# ICM20602.net
KiCad netlist of a schematic drawn in Altium Designer
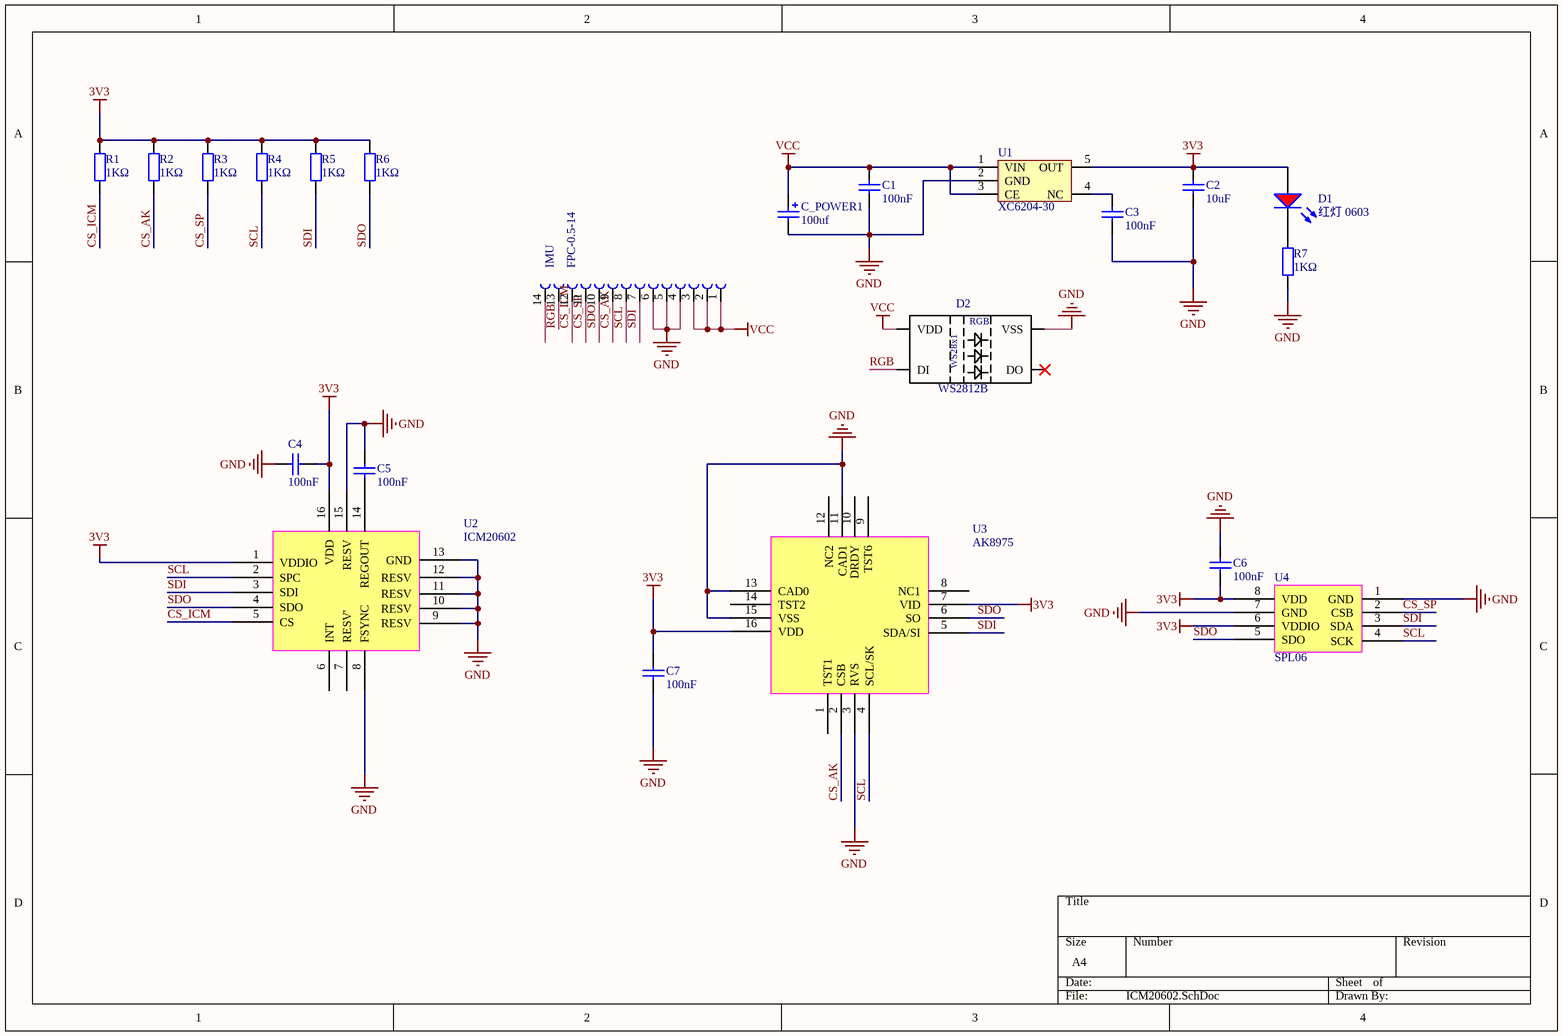
[diagram p0: ICM20602.SchDoc]

(export (version "E")
  (design (tool "Eeschema 10.0.6"))
  (components
    (comp (ref "C1")
      (value "100nF")
      (footprint "0603_C")
      (description "贴片电容")
      (libsource (lib "Miscellaneous Devices LC") (part "0603 100nF (104) 10% 50V"))
    )
    (comp (ref "C2")
      (value "10uF")
      (footprint "0603_C")
      (description "贴片电容")
      (libsource (lib "Miscellaneous Devices LC") (part "0603 10uF (106) 10% 10V"))
    )
    (comp (ref "C3")
      (value "100nF")
      (footprint "0603_C")
      (description "贴片电容")
      (libsource (lib "Miscellaneous Devices LC") (part "0603 100nF (104) 10% 50V"))
    )
    (comp (ref "C4")
      (value "100nF")
      (footprint "0603_C")
      (description "贴片电容")
      (libsource (lib "Miscellaneous Devices LC") (part "0603 100nF (104) 10% 50V"))
    )
    (comp (ref "C5")
      (value "100nF")
      (footprint "0603_C")
      (description "贴片电容")
      (libsource (lib "Miscellaneous Devices LC") (part "0603 100nF (104) 10% 50V"))
    )
    (comp (ref "C6")
      (value "100nF")
      (footprint "0603_C")
      (description "贴片电容")
      (libsource (lib "Miscellaneous Devices LC") (part "0603 100nF (104) 10% 50V"))
    )
    (comp (ref "C7")
      (value "100nF")
      (footprint "0603_C")
      (description "贴片电容")
      (libsource (lib "Miscellaneous Devices LC") (part "0603 100nF (104) 10% 50V"))
    )
    (comp (ref "C_POWER1")
      (value "100uf")
      (footprint "C1206")
      (description "Polarized Capacitor (Surface Mount)")
      (fields (field (name "PUBLISHER") "Altium Limited"))
      (libsource (lib "fly_smart") (part "Cap Pol3"))
    )
    (comp (ref "D1")
      (value "红灯 0603")
      (footprint "0603_LED_S1")
      (description "发光二极管")
      (libsource (lib "Miscellaneous Devices LC") (part "0603 红灯"))
    )
    (comp (ref "D2")
      (value "WS2812B")
      (footprint "WS2812B")
      (description "Intelligent Control Led Integrated Light Source Pack Of 10")
      (fields (field (name "MF") "Seeed Technology"))
      (libsource (lib "MyLib") (part "WS2812B"))
    )
    (comp (ref "IMU")
      (value "FPC-0.5-14")
      (footprint "FPC-0.5-14")
      (description "FFC / FPC Board Connector, WR-FPC Series, Surface Mount, Receptacle, 14, Bottom, 0.5 mm")
      (fields (field (name "MP") "687114149022") (field (name "MF") "Wurth Electronics"))
      (libsource (lib "MyLib") (part "FPC-0.5-14"))
    )
    (comp (ref "R1")
      (value "1KΩ")
      (footprint "0603_R")
      (description "贴片电阻")
      (libsource (lib "Miscellaneous Devices LC") (part "0603 1KΩ (1001) 1%"))
    )
    (comp (ref "R2")
      (value "1KΩ")
      (footprint "0603_R")
      (description "贴片电阻")
      (libsource (lib "Miscellaneous Devices LC") (part "0603 1KΩ (1001) 1%"))
    )
    (comp (ref "R3")
      (value "1KΩ")
      (footprint "0603_R")
      (description "贴片电阻")
      (libsource (lib "Miscellaneous Devices LC") (part "0603 1KΩ (1001) 1%"))
    )
    (comp (ref "R4")
      (value "1KΩ")
      (footprint "0603_R")
      (description "贴片电阻")
      (libsource (lib "Miscellaneous Devices LC") (part "0603 1KΩ (1001) 1%"))
    )
    (comp (ref "R5")
      (value "1KΩ")
      (footprint "0603_R")
      (description "贴片电阻")
      (libsource (lib "Miscellaneous Devices LC") (part "0603 1KΩ (1001) 1%"))
    )
    (comp (ref "R6")
      (value "1KΩ")
      (footprint "0603_R")
      (description "贴片电阻")
      (libsource (lib "Miscellaneous Devices LC") (part "0603 1KΩ (1001) 1%"))
    )
    (comp (ref "R7")
      (value "1KΩ")
      (footprint "0603_R")
      (description "贴片电阻")
      (libsource (lib "Miscellaneous Devices LC") (part "0603 1KΩ (1001) 1%"))
    )
    (comp (ref "U1") (value "XC6204-30") (footprint "SOT23-5S") (libsource (lib "MiniFly ") (part "XC6204")))
    (comp (ref "U2")
      (value "ICM20602")
      (footprint "ICM20602")
      (libsource (lib "TM4C_Series") (part "ICM20602"))
    )
    (comp (ref "U3") (value "AK8975") (footprint "AK8975") (libsource (lib "TM4C_Series") (part "AK8975")))
    (comp (ref "U4") (value "SPL06") (footprint "LGA-2_5X2MM") (libsource (lib "TM4C_Series") (part "SPL06")))
  )
  (nets
    (net (code "1") (name "/CS_AK") (class "Default")
      (node (ref "IMU") (pin "9") (pinfunction "6_9") (pintype "passive"))
      (node (ref "R2") (pin "1") (pinfunction "1_1") (pintype "passive"))
      (node (ref "U3") (pin "2") (pinfunction "CSB_2") (pintype "passive"))
    )
    (net (code "2") (name "/CS_ICM") (class "Default")
      (node (ref "IMU") (pin "12") (pinfunction "3_12") (pintype "passive"))
      (node (ref "R1") (pin "1") (pinfunction "1_1") (pintype "passive"))
      (node (ref "U2") (pin "5") (pinfunction "CS_5") (pintype "passive"))
    )
    (net (code "3") (name "/CS_SP") (class "Default")
      (node (ref "IMU") (pin "11") (pinfunction "4_11") (pintype "passive"))
      (node (ref "R3") (pin "1") (pinfunction "1_1") (pintype "passive"))
      (node (ref "U4") (pin "2") (pinfunction "CSB_2") (pintype "passive"))
    )
    (net (code "4") (name "/RGB") (class "Default")
      (node (ref "D2") (pin "4") (pinfunction "DI_4") (pintype "bidirectional"))
      (node (ref "IMU") (pin "13") (pinfunction "2_13") (pintype "passive"))
    )
    (net (code "5") (name "/SCL") (class "Default")
      (node (ref "IMU") (pin "8") (pinfunction "7_8") (pintype "passive"))
      (node (ref "R4") (pin "1") (pinfunction "1_1") (pintype "passive"))
      (node (ref "U2") (pin "2") (pinfunction "SPC_2") (pintype "passive"))
      (node (ref "U3") (pin "4") (pinfunction "SCL/SK_4") (pintype "passive"))
      (node (ref "U4") (pin "4") (pinfunction "SCK_4") (pintype "passive"))
    )
    (net (code "6") (name "/SDI") (class "Default")
      (node (ref "IMU") (pin "7") (pinfunction "8_7") (pintype "passive"))
      (node (ref "R5") (pin "1") (pinfunction "1_1") (pintype "passive"))
      (node (ref "U2") (pin "3") (pinfunction "SDI_3") (pintype "passive"))
      (node (ref "U3") (pin "5") (pinfunction "SDA/SI_5") (pintype "passive"))
      (node (ref "U4") (pin "3") (pinfunction "SDA_3") (pintype "passive"))
    )
    (net (code "7") (name "/SDO") (class "Default")
      (node (ref "IMU") (pin "10") (pinfunction "5_10") (pintype "passive"))
      (node (ref "R6") (pin "1") (pinfunction "1_1") (pintype "passive"))
      (node (ref "U2") (pin "4") (pinfunction "SDO_4") (pintype "passive"))
      (node (ref "U3") (pin "6") (pinfunction "SO_6") (pintype "passive"))
      (node (ref "U4") (pin "5") (pinfunction "SDO_5") (pintype "passive"))
    )
    (net (code "8") (name "3V3") (class "Default")
      (node (ref "C2") (pin "2") (pinfunction "2_2") (pintype "passive"))
      (node (ref "C4") (pin "2") (pinfunction "2_2") (pintype "passive"))
      (node (ref "C6") (pin "1") (pinfunction "1_1") (pintype "passive"))
      (node (ref "C7") (pin "2") (pinfunction "2_2") (pintype "passive"))
      (node (ref "D1") (pin "A") (pinfunction "A_A") (pintype "passive"))
      (node (ref "R1") (pin "2") (pinfunction "2_2") (pintype "passive"))
      (node (ref "R2") (pin "2") (pinfunction "2_2") (pintype "passive"))
      (node (ref "R3") (pin "2") (pinfunction "2_2") (pintype "passive"))
      (node (ref "R4") (pin "2") (pinfunction "2_2") (pintype "passive"))
      (node (ref "R5") (pin "2") (pinfunction "2_2") (pintype "passive"))
      (node (ref "R6") (pin "2") (pinfunction "2_2") (pintype "passive"))
      (node (ref "U1") (pin "5") (pinfunction "OUT_5") (pintype "passive"))
      (node (ref "U2") (pin "1") (pinfunction "VDDIO_1") (pintype "passive"))
      (node (ref "U2") (pin "16") (pinfunction "VDD_16") (pintype "passive"))
      (node (ref "U3") (pin "16") (pinfunction "VDD_16") (pintype "passive"))
      (node (ref "U3") (pin "7") (pinfunction "VID_7") (pintype "passive"))
      (node (ref "U4") (pin "6") (pinfunction "VDDIO_6") (pintype "passive"))
      (node (ref "U4") (pin "8") (pinfunction "VDD_8") (pintype "passive"))
    )
    (net (code "9") (name "GND") (class "Default")
      (node (ref "C1") (pin "1") (pinfunction "1_1") (pintype "passive"))
      (node (ref "C2") (pin "1") (pinfunction "1_1") (pintype "passive"))
      (node (ref "C3") (pin "1") (pinfunction "1_1") (pintype "passive"))
      (node (ref "C4") (pin "1") (pinfunction "1_1") (pintype "passive"))
      (node (ref "C5") (pin "1") (pinfunction "1_1") (pintype "passive"))
      (node (ref "C6") (pin "2") (pinfunction "2_2") (pintype "passive"))
      (node (ref "C7") (pin "1") (pinfunction "1_1") (pintype "passive"))
      (node (ref "C_POWER1") (pin "2") (pinfunction "2_2") (pintype "passive"))
      (node (ref "D2") (pin "3") (pinfunction "VSS_3") (pintype "bidirectional"))
      (node (ref "IMU") (pin "4") (pinfunction "11_4") (pintype "passive"))
      (node (ref "IMU") (pin "5") (pinfunction "10_5") (pintype "passive"))
      (node (ref "IMU") (pin "6") (pinfunction "9_6") (pintype "passive"))
      (node (ref "R7") (pin "1") (pinfunction "1_1") (pintype "passive"))
      (node (ref "U1") (pin "2") (pinfunction "GND_2") (pintype "passive"))
      (node (ref "U2") (pin "10") (pinfunction "RESV_10") (pintype "passive"))
      (node (ref "U2") (pin "11") (pinfunction "RESV_11") (pintype "passive"))
      (node (ref "U2") (pin "12") (pinfunction "RESV_12") (pintype "passive"))
      (node (ref "U2") (pin "13") (pinfunction "GND_13") (pintype "passive"))
      (node (ref "U2") (pin "15") (pinfunction "RESV_15") (pintype "passive"))
      (node (ref "U2") (pin "8") (pinfunction "FSYNC_8") (pintype "passive"))
      (node (ref "U2") (pin "9") (pinfunction "RESV_9") (pintype "passive"))
      (node (ref "U3") (pin "11") (pinfunction "CAD1_11") (pintype "passive"))
      (node (ref "U3") (pin "13") (pinfunction "CAD0_13") (pintype "passive"))
      (node (ref "U3") (pin "15") (pinfunction "VSS_15") (pintype "passive"))
      (node (ref "U3") (pin "3") (pinfunction "RVS_3") (pintype "passive"))
      (node (ref "U4") (pin "1") (pinfunction "GND_1") (pintype "passive"))
      (node (ref "U4") (pin "7") (pinfunction "GND_7") (pintype "passive"))
    )
    (net (code "10") (name "Net-(D1-PadK)") (class "Default")
      (node (ref "D1") (pin "K") (pinfunction "K_K") (pintype "passive"))
      (node (ref "R7") (pin "2") (pinfunction "2_2") (pintype "passive"))
    )
    (net (code "11") (name "Net-(U1-NC)") (class "Default")
      (node (ref "C3") (pin "2") (pinfunction "2_2") (pintype "passive"))
      (node (ref "U1") (pin "4") (pinfunction "NC_4") (pintype "passive"))
    )
    (net (code "12") (name "Net-(U2-REGOUT)") (class "Default")
      (node (ref "C5") (pin "2") (pinfunction "2_2") (pintype "passive"))
      (node (ref "U2") (pin "14") (pinfunction "REGOUT_14") (pintype "passive"))
    )
    (net (code "13") (name "VCC") (class "Default")
      (node (ref "C1") (pin "2") (pinfunction "2_2") (pintype "passive"))
      (node (ref "C_POWER1") (pin "1") (pinfunction "1_1") (pintype "passive"))
      (node (ref "D2") (pin "1") (pinfunction "VDD_1") (pintype "bidirectional"))
      (node (ref "IMU") (pin "1") (pinfunction "14_1") (pintype "passive"))
      (node (ref "IMU") (pin "2") (pinfunction "13_2") (pintype "passive"))
      (node (ref "IMU") (pin "3") (pinfunction "12_3") (pintype "passive"))
      (node (ref "U1") (pin "1") (pinfunction "VIN_1") (pintype "passive"))
      (node (ref "U1") (pin "3") (pinfunction "CE_3") (pintype "passive"))
    )
    (net (code "14") (name "unconnected-(D2-DO-Pad2)") (class "Default")
      (node (ref "D2") (pin "2") (pinfunction "DO_2") (pintype "bidirectional+no_connect"))
    )
    (net (code "15") (name "unconnected-(IMU-1-Pad14)") (class "Default")
      (node (ref "IMU") (pin "14") (pinfunction "1_14") (pintype "passive"))
    )
    (net (code "16") (name "unconnected-(U2-INT-Pad6)") (class "Default")
      (node (ref "U2") (pin "6") (pinfunction "INT_6") (pintype "passive"))
    )
    (net (code "17") (name "unconnected-(U2-RESV'-Pad7)") (class "Default")
      (node (ref "U2") (pin "7") (pinfunction "RESV'_7") (pintype "passive"))
    )
    (net (code "18") (name "unconnected-(U3-DRDY-Pad10)") (class "Default")
      (node (ref "U3") (pin "10") (pinfunction "DRDY_10") (pintype "passive"))
    )
    (net (code "19") (name "unconnected-(U3-NC1-Pad8)") (class "Default")
      (node (ref "U3") (pin "8") (pinfunction "NC1_8") (pintype "passive"))
    )
    (net (code "20") (name "unconnected-(U3-NC2-Pad12)") (class "Default")
      (node (ref "U3") (pin "12") (pinfunction "NC2_12") (pintype "passive"))
    )
    (net (code "21") (name "unconnected-(U3-TST1-Pad1)") (class "Default")
      (node (ref "U3") (pin "1") (pinfunction "TST1_1") (pintype "passive"))
    )
    (net (code "22") (name "unconnected-(U3-TST2-Pad14)") (class "Default")
      (node (ref "U3") (pin "14") (pinfunction "TST2_14") (pintype "passive"))
    )
    (net (code "23") (name "unconnected-(U3-TST6-Pad9)") (class "Default")
      (node (ref "U3") (pin "9") (pinfunction "TST6_9") (pintype "passive"))
    )
  )
)
